# FPGA_SDRAM2.net
KiCad netlist of a schematic drawn in Altium Designer
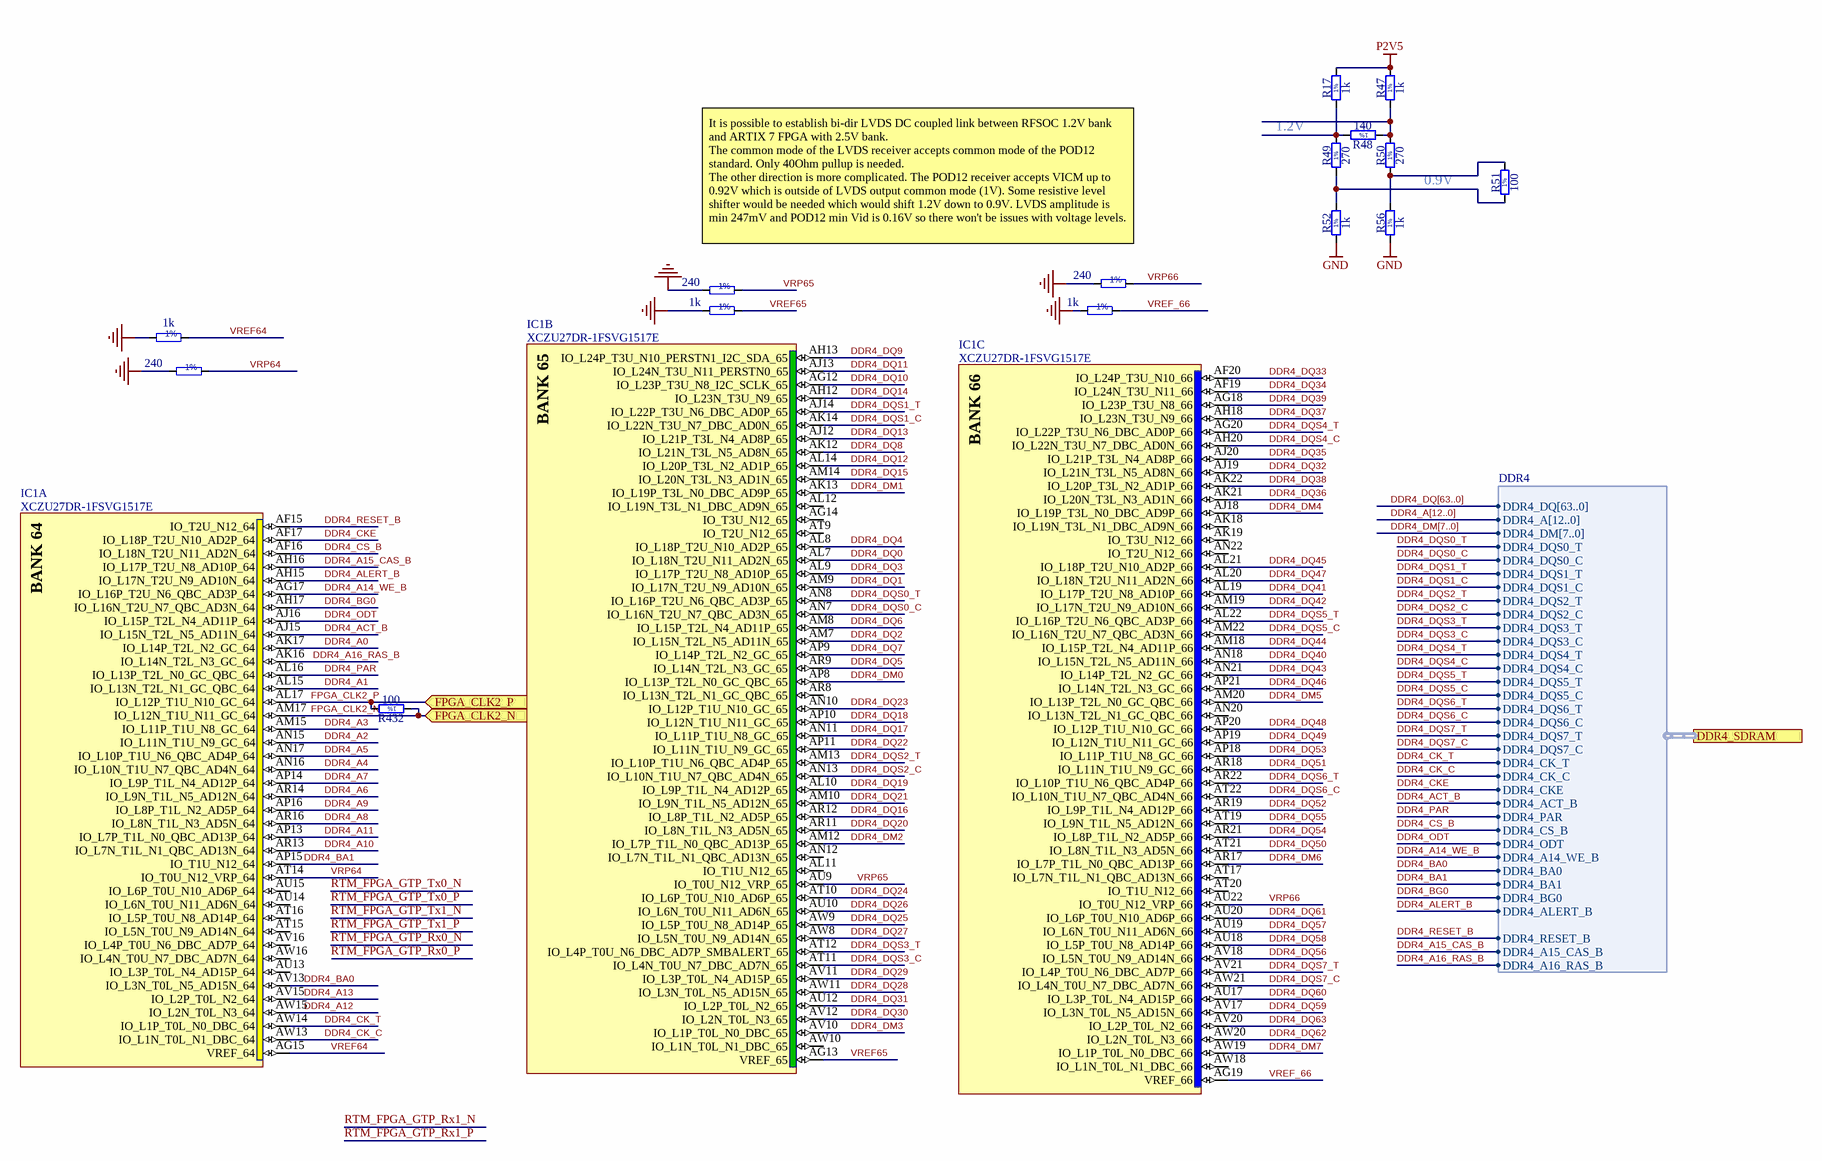
[diagram p0: FPGA_SDRAM2.SchDoc]

(export (version "E")
  (design (tool "Eeschema 10.0.6"))
  (components
    (comp (ref "IC1")
      (value "XCZU27DR-1FSVG1517E")
      (footprint "XILINX_FSVG1517 (XCZU27DR)")
      (fields (field (name "MANUFACTURER") "XILINX") (field (name "AUTHOR") "CERN DEM MR"))
      (libsource (lib "ICs And Semiconductors") (part "XCZU27DR-1FSVG1517E"))
    )
    (comp (ref "R1")
      (value "1k")
      (fields
        (field (name "$$NOTCOMMONPROPERTY_GENERAL PART NUMBER") "R0402_1K_1%_0.0625W_100PPM")
        (field (name "$$NOTCOMMONPROPERTY_MANUFACTURER1 PART NUMBER") "232270671002L")
        (field (name "MANUFACTURER") "GENERIC")
      )
      (libsource (lib "altium-import") (part "root_0__*"))
    )
    (comp (ref "R2")
      (value "240")
      (fields
        (field (name "$$NOTCOMMONPROPERTY_GENERAL PART NUMBER") "R0402_240R_1%_0.0625W_100PPM")
        (field (name "$$NOTCOMMONPROPERTY_MANUFACTURER1 PART NUMBER") "232270672401L")
        (field (name "MANUFACTURER") "GENERIC")
      )
      (libsource (lib "altium-import") (part "root_0__*"))
    )
    (comp (ref "R3")
      (value "240")
      (fields
        (field (name "$$NOTCOMMONPROPERTY_GENERAL PART NUMBER") "R0402_240R_1%_0.0625W_100PPM")
        (field (name "$$NOTCOMMONPROPERTY_MANUFACTURER1 PART NUMBER") "232270672401L")
        (field (name "MANUFACTURER") "GENERIC")
      )
      (libsource (lib "altium-import") (part "root_0__*"))
    )
    (comp (ref "R4")
      (value "240")
      (fields
        (field (name "$$NOTCOMMONPROPERTY_GENERAL PART NUMBER") "R0402_240R_1%_0.0625W_100PPM")
        (field (name "$$NOTCOMMONPROPERTY_MANUFACTURER1 PART NUMBER") "232270672401L")
        (field (name "MANUFACTURER") "GENERIC")
      )
      (libsource (lib "altium-import") (part "root_0__*"))
    )
    (comp (ref "R5")
      (value "1k")
      (fields
        (field (name "$$NOTCOMMONPROPERTY_GENERAL PART NUMBER") "R0402_1K_1%_0.0625W_100PPM")
        (field (name "$$NOTCOMMONPROPERTY_MANUFACTURER1 PART NUMBER") "232270671002L")
        (field (name "MANUFACTURER") "GENERIC")
      )
      (libsource (lib "altium-import") (part "root_0__*"))
    )
    (comp (ref "R6")
      (value "1k")
      (fields
        (field (name "$$NOTCOMMONPROPERTY_GENERAL PART NUMBER") "R0402_1K_1%_0.0625W_100PPM")
        (field (name "$$NOTCOMMONPROPERTY_MANUFACTURER1 PART NUMBER") "232270671002L")
        (field (name "MANUFACTURER") "GENERIC")
      )
      (libsource (lib "altium-import") (part "root_0__*"))
    )
    (comp (ref "R17")
      (value "1k")
      (footprint "RESC1005X40N")
      (description "Resistor - 1%")
      (fields
        (field (name "PART NUMBER") "R0402_1K_1%_0.0625W_100PPM")
        (field (name "POWER") "0.0625W")
        (field (name "AUTHOR") "CERN DEM JLC")
      )
      (libsource (lib "Resistors") (part "Resistor - 1%"))
    )
    (comp (ref "R47")
      (value "1k")
      (footprint "RESC1005X40N")
      (description "Resistor - 1%")
      (fields
        (field (name "PART NUMBER") "R0402_1K_1%_0.0625W_100PPM")
        (field (name "POWER") "0.0625W")
        (field (name "AUTHOR") "CERN DEM JLC")
      )
      (libsource (lib "Resistors") (part "Resistor - 1%"))
    )
    (comp (ref "R48")
      (value "140")
      (footprint "RESC1005X40N")
      (description "Resistor - 1%")
      (fields
        (field (name "PART NUMBER") "R0402_140R_1%_0.0625W_100PPM")
        (field (name "POWER") "0.0625W")
        (field (name "AUTHOR") "CERN DEM BC")
      )
      (libsource (lib "Resistors") (part "Resistor - 1%"))
    )
    (comp (ref "R49")
      (value "270")
      (footprint "RESC1005X40N")
      (description "Resistor - 1%")
      (fields
        (field (name "PART NUMBER") "R0402_270R_1%_0.0625W_100PPM")
        (field (name "POWER") "0.0625W")
        (field (name "AUTHOR") "CERN DEM JLC")
      )
      (libsource (lib "Resistors") (part "Resistor - 1%"))
    )
    (comp (ref "R50")
      (value "270")
      (footprint "RESC1005X40N")
      (description "Resistor - 1%")
      (fields
        (field (name "PART NUMBER") "R0402_270R_1%_0.0625W_100PPM")
        (field (name "POWER") "0.0625W")
        (field (name "AUTHOR") "CERN DEM JLC")
      )
      (libsource (lib "Resistors") (part "Resistor - 1%"))
    )
    (comp (ref "R51")
      (value "100")
      (footprint "RESC1005X40N")
      (description "Resistor - 1%")
      (fields
        (field (name "PART NUMBER") "R0402_100R_1%_0.0625W_100PPM")
        (field (name "POWER") "0.0625W")
        (field (name "AUTHOR") "CERN DEM JLC")
      )
      (libsource (lib "Resistors") (part "Resistor - 1%"))
    )
    (comp (ref "R52")
      (value "1k")
      (footprint "RESC1005X40N")
      (description "Resistor - 1%")
      (fields
        (field (name "PART NUMBER") "R0402_1K_1%_0.0625W_100PPM")
        (field (name "POWER") "0.0625W")
        (field (name "AUTHOR") "CERN DEM JLC")
      )
      (libsource (lib "Resistors") (part "Resistor - 1%"))
    )
    (comp (ref "R56")
      (value "1k")
      (footprint "RESC1005X40N")
      (description "Resistor - 1%")
      (fields
        (field (name "PART NUMBER") "R0402_1K_1%_0.0625W_100PPM")
        (field (name "POWER") "0.0625W")
        (field (name "AUTHOR") "CERN DEM JLC")
      )
      (libsource (lib "Resistors") (part "Resistor - 1%"))
    )
    (comp (ref "R432")
      (value "100")
      (footprint "RESC1005X40N")
      (description "Resistor - 1%")
      (fields
        (field (name "MANUFACTURER PART NUMBER") "R0402_100R_1%_0.0625W_100PPM")
        (field (name "MANUFACTURER") "GENERIC")
        (field (name "AUTHOR") "CERN DEM JLC")
      )
      (libsource (lib "Resistors") (part "Resistor - 1%"))
    )
  )
  (nets
    (net (code "2") (name "/DDR4_A0") (class "Default")
      (node (ref "IC1") (pin "AK17") (pinfunction "IO_L14P_T2L_N2_GC_64_AK17") (pintype "bidirectional"))
    )
    (net (code "3") (name "/DDR4_A1") (class "Default")
      (node (ref "IC1") (pin "AL15") (pinfunction "IO_L13N_T2L_N1_GC_QBC_64_AL15") (pintype "bidirectional"))
    )
    (net (code "4") (name "/DDR4_A2") (class "Default")
      (node (ref "IC1") (pin "AN15") (pinfunction "IO_L11N_T1U_N9_GC_64_AN15") (pintype "bidirectional"))
    )
    (net (code "5") (name "/DDR4_A3") (class "Default")
      (node (ref "IC1") (pin "AM15") (pinfunction "IO_L11P_T1U_N8_GC_64_AM15") (pintype "bidirectional"))
    )
    (net (code "6") (name "/DDR4_A4") (class "Default")
      (node (ref "IC1") (pin "AN16") (pinfunction "IO_L10N_T1U_N7_QBC_AD4N_64_AN16") (pintype "bidirectional"))
    )
    (net (code "7") (name "/DDR4_A5") (class "Default")
      (node (ref "IC1") (pin "AN17") (pinfunction "IO_L10P_T1U_N6_QBC_AD4P_64_AN17") (pintype "bidirectional"))
    )
    (net (code "8") (name "/DDR4_A6") (class "Default")
      (node (ref "IC1") (pin "AR14") (pinfunction "IO_L9N_T1L_N5_AD12N_64_AR14") (pintype "bidirectional"))
    )
    (net (code "9") (name "/DDR4_A7") (class "Default")
      (node (ref "IC1") (pin "AP14") (pinfunction "IO_L9P_T1L_N4_AD12P_64_AP14") (pintype "bidirectional"))
    )
    (net (code "10") (name "/DDR4_A8") (class "Default")
      (node (ref "IC1") (pin "AR16") (pinfunction "IO_L8N_T1L_N3_AD5N_64_AR16") (pintype "bidirectional"))
    )
    (net (code "11") (name "/DDR4_A9") (class "Default")
      (node (ref "IC1") (pin "AP16") (pinfunction "IO_L8P_T1L_N2_AD5P_64_AP16") (pintype "bidirectional"))
    )
    (net (code "12") (name "/DDR4_A10") (class "Default")
      (node (ref "IC1") (pin "AR13") (pinfunction "IO_L7N_T1L_N1_QBC_AD13N_64_AR13") (pintype "bidirectional"))
    )
    (net (code "13") (name "/DDR4_A11") (class "Default")
      (node (ref "IC1") (pin "AP13") (pinfunction "IO_L7P_T1L_N0_QBC_AD13P_64_AP13") (pintype "bidirectional"))
    )
    (net (code "14") (name "/DDR4_A12") (class "Default")
      (node (ref "IC1") (pin "AW15") (pinfunction "IO_L2N_T0L_N3_64_AW15") (pintype "bidirectional"))
    )
    (net (code "15") (name "/DDR4_A13") (class "Default")
      (node (ref "IC1") (pin "AV15") (pinfunction "IO_L2P_T0L_N2_64_AV15") (pintype "bidirectional"))
    )
    (net (code "16") (name "/DDR4_A14_WE_B") (class "Default")
      (node (ref "IC1") (pin "AG17") (pinfunction "IO_L16P_T2U_N6_QBC_AD3P_64_AG17") (pintype "bidirectional"))
    )
    (net (code "17") (name "/DDR4_A15_CAS_B") (class "Default")
      (node (ref "IC1") (pin "AH16") (pinfunction "IO_L17P_T2U_N8_AD10P_64_AH16") (pintype "bidirectional"))
    )
    (net (code "18") (name "/DDR4_A16_RAS_B") (class "Default")
      (node (ref "IC1") (pin "AK16") (pinfunction "IO_L14N_T2L_N3_GC_64_AK16") (pintype "bidirectional"))
    )
    (net (code "19") (name "/DDR4_ACT_B") (class "Default")
      (node (ref "IC1") (pin "AJ15") (pinfunction "IO_L15N_T2L_N5_AD11N_64_AJ15") (pintype "bidirectional"))
    )
    (net (code "20") (name "/DDR4_ALERT_B") (class "Default")
      (node (ref "IC1") (pin "AH15") (pinfunction "IO_L17N_T2U_N9_AD10N_64_AH15") (pintype "bidirectional"))
    )
    (net (code "22") (name "/DDR4_BA0") (class "Default")
      (node (ref "IC1") (pin "AV13") (pinfunction "IO_L3N_T0L_N5_AD15N_64_AV13") (pintype "bidirectional"))
    )
    (net (code "23") (name "/DDR4_BA1") (class "Default")
      (node (ref "IC1") (pin "AP15") (pinfunction "IO_T1U_N12_64_AP15") (pintype "bidirectional"))
    )
    (net (code "24") (name "/DDR4_BG0") (class "Default")
      (node (ref "IC1") (pin "AH17") (pinfunction "IO_L16N_T2U_N7_QBC_AD3N_64_AH17") (pintype "bidirectional"))
    )
    (net (code "25") (name "/DDR4_CKE") (class "Default")
      (node (ref "IC1") (pin "AF17") (pinfunction "IO_L18P_T2U_N10_AD2P_64_AF17") (pintype "bidirectional"))
    )
    (net (code "26") (name "/DDR4_CK_C") (class "Default")
      (node (ref "IC1") (pin "AW13") (pinfunction "IO_L1N_T0L_N1_DBC_64_AW13") (pintype "bidirectional"))
    )
    (net (code "27") (name "/DDR4_CK_T") (class "Default")
      (node (ref "IC1") (pin "AW14") (pinfunction "IO_L1P_T0L_N0_DBC_64_AW14") (pintype "bidirectional"))
    )
    (net (code "28") (name "/DDR4_CS_B") (class "Default")
      (node (ref "IC1") (pin "AF16") (pinfunction "IO_L18N_T2U_N11_AD2N_64_AF16") (pintype "bidirectional"))
    )
    (net (code "29") (name "/DDR4_DM0") (class "Default")
      (node (ref "IC1") (pin "AP8") (pinfunction "IO_L13P_T2L_N0_GC_QBC_65_AP8") (pintype "bidirectional"))
    )
    (net (code "30") (name "/DDR4_DM1") (class "Default")
      (node (ref "IC1") (pin "AK13") (pinfunction "IO_L19P_T3L_N0_DBC_AD9P_65_AK13") (pintype "bidirectional"))
    )
    (net (code "31") (name "/DDR4_DM2") (class "Default")
      (node (ref "IC1") (pin "AM12") (pinfunction "IO_L7P_T1L_N0_QBC_AD13P_65_AM12") (pintype "bidirectional"))
    )
    (net (code "32") (name "/DDR4_DM3") (class "Default")
      (node (ref "IC1") (pin "AV10") (pinfunction "IO_L1P_T0L_N0_DBC_65_AV10") (pintype "bidirectional"))
    )
    (net (code "33") (name "/DDR4_DM4") (class "Default")
      (node (ref "IC1") (pin "AJ18") (pinfunction "IO_L19P_T3L_N0_DBC_AD9P_66_AJ18") (pintype "bidirectional"))
    )
    (net (code "34") (name "/DDR4_DM5") (class "Default")
      (node (ref "IC1") (pin "AM20") (pinfunction "IO_L13P_T2L_N0_GC_QBC_66_AM20") (pintype "bidirectional"))
    )
    (net (code "35") (name "/DDR4_DM6") (class "Default")
      (node (ref "IC1") (pin "AR17") (pinfunction "IO_L7P_T1L_N0_QBC_AD13P_66_AR17") (pintype "bidirectional"))
    )
    (net (code "36") (name "/DDR4_DM7") (class "Default")
      (node (ref "IC1") (pin "AW19") (pinfunction "IO_L1P_T0L_N0_DBC_66_AW19") (pintype "bidirectional"))
    )
    (net (code "37") (name "/DDR4_DQ0") (class "Default")
      (node (ref "IC1") (pin "AL7") (pinfunction "IO_L18N_T2U_N11_AD2N_65_AL7") (pintype "bidirectional"))
    )
    (net (code "38") (name "/DDR4_DQ1") (class "Default")
      (node (ref "IC1") (pin "AM9") (pinfunction "IO_L17N_T2U_N9_AD10N_65_AM9") (pintype "bidirectional"))
    )
    (net (code "39") (name "/DDR4_DQ2") (class "Default")
      (node (ref "IC1") (pin "AM7") (pinfunction "IO_L15N_T2L_N5_AD11N_65_AM7") (pintype "bidirectional"))
    )
    (net (code "40") (name "/DDR4_DQ3") (class "Default")
      (node (ref "IC1") (pin "AL9") (pinfunction "IO_L17P_T2U_N8_AD10P_65_AL9") (pintype "bidirectional"))
    )
    (net (code "41") (name "/DDR4_DQ4") (class "Default")
      (node (ref "IC1") (pin "AL8") (pinfunction "IO_L18P_T2U_N10_AD2P_65_AL8") (pintype "bidirectional"))
    )
    (net (code "42") (name "/DDR4_DQ5") (class "Default")
      (node (ref "IC1") (pin "AR9") (pinfunction "IO_L14N_T2L_N3_GC_65_AR9") (pintype "bidirectional"))
    )
    (net (code "43") (name "/DDR4_DQ6") (class "Default")
      (node (ref "IC1") (pin "AM8") (pinfunction "IO_L15P_T2L_N4_AD11P_65_AM8") (pintype "bidirectional"))
    )
    (net (code "44") (name "/DDR4_DQ7") (class "Default")
      (node (ref "IC1") (pin "AP9") (pinfunction "IO_L14P_T2L_N2_GC_65_AP9") (pintype "bidirectional"))
    )
    (net (code "45") (name "/DDR4_DQ8") (class "Default")
      (node (ref "IC1") (pin "AK12") (pinfunction "IO_L21N_T3L_N5_AD8N_65_AK12") (pintype "bidirectional"))
    )
    (net (code "46") (name "/DDR4_DQ9") (class "Default")
      (node (ref "IC1") (pin "AH13") (pinfunction "IO_L24P_T3U_N10_PERSTN1_I2C_SDA_65_AH13") (pintype "bidirectional"))
    )
    (net (code "47") (name "/DDR4_DQ10") (class "Default")
      (node (ref "IC1") (pin "AG12") (pinfunction "IO_L23P_T3U_N8_I2C_SCLK_65_AG12") (pintype "bidirectional"))
    )
    (net (code "48") (name "/DDR4_DQ11") (class "Default")
      (node (ref "IC1") (pin "AJ13") (pinfunction "IO_L24N_T3U_N11_PERSTN0_65_AJ13") (pintype "bidirectional"))
    )
    (net (code "49") (name "/DDR4_DQ12") (class "Default")
      (node (ref "IC1") (pin "AL14") (pinfunction "IO_L20P_T3L_N2_AD1P_65_AL14") (pintype "bidirectional"))
    )
    (net (code "50") (name "/DDR4_DQ13") (class "Default")
      (node (ref "IC1") (pin "AJ12") (pinfunction "IO_L21P_T3L_N4_AD8P_65_AJ12") (pintype "bidirectional"))
    )
    (net (code "51") (name "/DDR4_DQ14") (class "Default")
      (node (ref "IC1") (pin "AH12") (pinfunction "IO_L23N_T3U_N9_65_AH12") (pintype "bidirectional"))
    )
    (net (code "52") (name "/DDR4_DQ15") (class "Default")
      (node (ref "IC1") (pin "AM14") (pinfunction "IO_L20N_T3L_N3_AD1N_65_AM14") (pintype "bidirectional"))
    )
    (net (code "53") (name "/DDR4_DQ16") (class "Default")
      (node (ref "IC1") (pin "AR12") (pinfunction "IO_L8P_T1L_N2_AD5P_65_AR12") (pintype "bidirectional"))
    )
    (net (code "54") (name "/DDR4_DQ17") (class "Default")
      (node (ref "IC1") (pin "AN11") (pinfunction "IO_L11P_T1U_N8_GC_65_AN11") (pintype "bidirectional"))
    )
    (net (code "55") (name "/DDR4_DQ18") (class "Default")
      (node (ref "IC1") (pin "AP10") (pinfunction "IO_L12N_T1U_N11_GC_65_AP10") (pintype "bidirectional"))
    )
    (net (code "56") (name "/DDR4_DQ19") (class "Default")
      (node (ref "IC1") (pin "AL10") (pinfunction "IO_L9P_T1L_N4_AD12P_65_AL10") (pintype "bidirectional"))
    )
    (net (code "57") (name "/DDR4_DQ20") (class "Default")
      (node (ref "IC1") (pin "AR11") (pinfunction "IO_L8N_T1L_N3_AD5N_65_AR11") (pintype "bidirectional"))
    )
    (net (code "58") (name "/DDR4_DQ21") (class "Default")
      (node (ref "IC1") (pin "AM10") (pinfunction "IO_L9N_T1L_N5_AD12N_65_AM10") (pintype "bidirectional"))
    )
    (net (code "59") (name "/DDR4_DQ22") (class "Default")
      (node (ref "IC1") (pin "AP11") (pinfunction "IO_L11N_T1U_N9_GC_65_AP11") (pintype "bidirectional"))
    )
    (net (code "60") (name "/DDR4_DQ23") (class "Default")
      (node (ref "IC1") (pin "AN10") (pinfunction "IO_L12P_T1U_N10_GC_65_AN10") (pintype "bidirectional"))
    )
    (net (code "61") (name "/DDR4_DQ24") (class "Default")
      (node (ref "IC1") (pin "AT10") (pinfunction "IO_L6P_T0U_N10_AD6P_65_AT10") (pintype "bidirectional"))
    )
    (net (code "62") (name "/DDR4_DQ25") (class "Default")
      (node (ref "IC1") (pin "AW9") (pinfunction "IO_L5P_T0U_N8_AD14P_65_AW9") (pintype "bidirectional"))
    )
    (net (code "63") (name "/DDR4_DQ26") (class "Default")
      (node (ref "IC1") (pin "AU10") (pinfunction "IO_L6N_T0U_N11_AD6N_65_AU10") (pintype "bidirectional"))
    )
    (net (code "64") (name "/DDR4_DQ27") (class "Default")
      (node (ref "IC1") (pin "AW8") (pinfunction "IO_L5N_T0U_N9_AD14N_65_AW8") (pintype "bidirectional"))
    )
    (net (code "65") (name "/DDR4_DQ28") (class "Default")
      (node (ref "IC1") (pin "AW11") (pinfunction "IO_L3N_T0L_N5_AD15N_65_AW11") (pintype "bidirectional"))
    )
    (net (code "66") (name "/DDR4_DQ29") (class "Default")
      (node (ref "IC1") (pin "AV11") (pinfunction "IO_L3P_T0L_N4_AD15P_65_AV11") (pintype "bidirectional"))
    )
    (net (code "67") (name "/DDR4_DQ30") (class "Default")
      (node (ref "IC1") (pin "AV12") (pinfunction "IO_L2N_T0L_N3_65_AV12") (pintype "bidirectional"))
    )
    (net (code "68") (name "/DDR4_DQ31") (class "Default")
      (node (ref "IC1") (pin "AU12") (pinfunction "IO_L2P_T0L_N2_65_AU12") (pintype "bidirectional"))
    )
    (net (code "69") (name "/DDR4_DQ32") (class "Default")
      (node (ref "IC1") (pin "AJ19") (pinfunction "IO_L21N_T3L_N5_AD8N_66_AJ19") (pintype "bidirectional"))
    )
    (net (code "70") (name "/DDR4_DQ33") (class "Default")
      (node (ref "IC1") (pin "AF20") (pinfunction "IO_L24P_T3U_N10_66_AF20") (pintype "bidirectional"))
    )
    (net (code "71") (name "/DDR4_DQ34") (class "Default")
      (node (ref "IC1") (pin "AF19") (pinfunction "IO_L24N_T3U_N11_66_AF19") (pintype "bidirectional"))
    )
    (net (code "72") (name "/DDR4_DQ35") (class "Default")
      (node (ref "IC1") (pin "AJ20") (pinfunction "IO_L21P_T3L_N4_AD8P_66_AJ20") (pintype "bidirectional"))
    )
    (net (code "73") (name "/DDR4_DQ36") (class "Default")
      (node (ref "IC1") (pin "AK21") (pinfunction "IO_L20N_T3L_N3_AD1N_66_AK21") (pintype "bidirectional"))
    )
    (net (code "74") (name "/DDR4_DQ37") (class "Default")
      (node (ref "IC1") (pin "AH18") (pinfunction "IO_L23N_T3U_N9_66_AH18") (pintype "bidirectional"))
    )
    (net (code "75") (name "/DDR4_DQ38") (class "Default")
      (node (ref "IC1") (pin "AK22") (pinfunction "IO_L20P_T3L_N2_AD1P_66_AK22") (pintype "bidirectional"))
    )
    (net (code "76") (name "/DDR4_DQ39") (class "Default")
      (node (ref "IC1") (pin "AG18") (pinfunction "IO_L23P_T3U_N8_66_AG18") (pintype "bidirectional"))
    )
    (net (code "77") (name "/DDR4_DQ40") (class "Default")
      (node (ref "IC1") (pin "AN18") (pinfunction "IO_L15N_T2L_N5_AD11N_66_AN18") (pintype "bidirectional"))
    )
    (net (code "78") (name "/DDR4_DQ41") (class "Default")
      (node (ref "IC1") (pin "AL19") (pinfunction "IO_L17P_T2U_N8_AD10P_66_AL19") (pintype "bidirectional"))
    )
    (net (code "79") (name "/DDR4_DQ42") (class "Default")
      (node (ref "IC1") (pin "AM19") (pinfunction "IO_L17N_T2U_N9_AD10N_66_AM19") (pintype "bidirectional"))
    )
    (net (code "80") (name "/DDR4_DQ43") (class "Default")
      (node (ref "IC1") (pin "AN21") (pinfunction "IO_L14P_T2L_N2_GC_66_AN21") (pintype "bidirectional"))
    )
    (net (code "81") (name "/DDR4_DQ44") (class "Default")
      (node (ref "IC1") (pin "AM18") (pinfunction "IO_L15P_T2L_N4_AD11P_66_AM18") (pintype "bidirectional"))
    )
    (net (code "82") (name "/DDR4_DQ45") (class "Default")
      (node (ref "IC1") (pin "AL21") (pinfunction "IO_L18P_T2U_N10_AD2P_66_AL21") (pintype "bidirectional"))
    )
    (net (code "83") (name "/DDR4_DQ46") (class "Default")
      (node (ref "IC1") (pin "AP21") (pinfunction "IO_L14N_T2L_N3_GC_66_AP21") (pintype "bidirectional"))
    )
    (net (code "84") (name "/DDR4_DQ47") (class "Default")
      (node (ref "IC1") (pin "AL20") (pinfunction "IO_L18N_T2U_N11_AD2N_66_AL20") (pintype "bidirectional"))
    )
    (net (code "85") (name "/DDR4_DQ48") (class "Default")
      (node (ref "IC1") (pin "AP20") (pinfunction "IO_L12P_T1U_N10_GC_66_AP20") (pintype "bidirectional"))
    )
    (net (code "86") (name "/DDR4_DQ49") (class "Default")
      (node (ref "IC1") (pin "AP19") (pinfunction "IO_L12N_T1U_N11_GC_66_AP19") (pintype "bidirectional"))
    )
    (net (code "87") (name "/DDR4_DQ50") (class "Default")
      (node (ref "IC1") (pin "AT21") (pinfunction "IO_L8N_T1L_N3_AD5N_66_AT21") (pintype "bidirectional"))
    )
    (net (code "88") (name "/DDR4_DQ51") (class "Default")
      (node (ref "IC1") (pin "AR18") (pinfunction "IO_L11N_T1U_N9_GC_66_AR18") (pintype "bidirectional"))
    )
    (net (code "89") (name "/DDR4_DQ52") (class "Default")
      (node (ref "IC1") (pin "AR19") (pinfunction "IO_L9P_T1L_N4_AD12P_66_AR19") (pintype "bidirectional"))
    )
    (net (code "90") (name "/DDR4_DQ53") (class "Default")
      (node (ref "IC1") (pin "AP18") (pinfunction "IO_L11P_T1U_N8_GC_66_AP18") (pintype "bidirectional"))
    )
    (net (code "91") (name "/DDR4_DQ54") (class "Default")
      (node (ref "IC1") (pin "AR21") (pinfunction "IO_L8P_T1L_N2_AD5P_66_AR21") (pintype "bidirectional"))
    )
    (net (code "92") (name "/DDR4_DQ55") (class "Default")
      (node (ref "IC1") (pin "AT19") (pinfunction "IO_L9N_T1L_N5_AD12N_66_AT19") (pintype "bidirectional"))
    )
    (net (code "93") (name "/DDR4_DQ56") (class "Default")
      (node (ref "IC1") (pin "AV18") (pinfunction "IO_L5N_T0U_N9_AD14N_66_AV18") (pintype "bidirectional"))
    )
    (net (code "94") (name "/DDR4_DQ57") (class "Default")
      (node (ref "IC1") (pin "AU19") (pinfunction "IO_L6N_T0U_N11_AD6N_66_AU19") (pintype "bidirectional"))
    )
    (net (code "95") (name "/DDR4_DQ58") (class "Default")
      (node (ref "IC1") (pin "AU18") (pinfunction "IO_L5P_T0U_N8_AD14P_66_AU18") (pintype "bidirectional"))
    )
    (net (code "96") (name "/DDR4_DQ59") (class "Default")
      (node (ref "IC1") (pin "AV17") (pinfunction "IO_L3N_T0L_N5_AD15N_66_AV17") (pintype "bidirectional"))
    )
    (net (code "97") (name "/DDR4_DQ60") (class "Default")
      (node (ref "IC1") (pin "AU17") (pinfunction "IO_L3P_T0L_N4_AD15P_66_AU17") (pintype "bidirectional"))
    )
    (net (code "98") (name "/DDR4_DQ61") (class "Default")
      (node (ref "IC1") (pin "AU20") (pinfunction "IO_L6P_T0U_N10_AD6P_66_AU20") (pintype "bidirectional"))
    )
    (net (code "99") (name "/DDR4_DQ62") (class "Default")
      (node (ref "IC1") (pin "AW20") (pinfunction "IO_L2N_T0L_N3_66_AW20") (pintype "bidirectional"))
    )
    (net (code "100") (name "/DDR4_DQ63") (class "Default")
      (node (ref "IC1") (pin "AV20") (pinfunction "IO_L2P_T0L_N2_66_AV20") (pintype "bidirectional"))
    )
    (net (code "101") (name "/DDR4_DQS0_C") (class "Default")
      (node (ref "IC1") (pin "AN7") (pinfunction "IO_L16N_T2U_N7_QBC_AD3N_65_AN7") (pintype "bidirectional"))
    )
    (net (code "102") (name "/DDR4_DQS0_T") (class "Default")
      (node (ref "IC1") (pin "AN8") (pinfunction "IO_L16P_T2U_N6_QBC_AD3P_65_AN8") (pintype "bidirectional"))
    )
    (net (code "103") (name "/DDR4_DQS1_C") (class "Default")
      (node (ref "IC1") (pin "AK14") (pinfunction "IO_L22N_T3U_N7_DBC_AD0N_65_AK14") (pintype "bidirectional"))
    )
    (net (code "104") (name "/DDR4_DQS1_T") (class "Default")
      (node (ref "IC1") (pin "AJ14") (pinfunction "IO_L22P_T3U_N6_DBC_AD0P_65_AJ14") (pintype "bidirectional"))
    )
    (net (code "105") (name "/DDR4_DQS2_C") (class "Default")
      (node (ref "IC1") (pin "AN13") (pinfunction "IO_L10N_T1U_N7_QBC_AD4N_65_AN13") (pintype "bidirectional"))
    )
    (net (code "106") (name "/DDR4_DQS2_T") (class "Default")
      (node (ref "IC1") (pin "AM13") (pinfunction "IO_L10P_T1U_N6_QBC_AD4P_65_AM13") (pintype "bidirectional"))
    )
    (net (code "107") (name "/DDR4_DQS3_C") (class "Default")
      (node (ref "IC1") (pin "AT11") (pinfunction "IO_L4N_T0U_N7_DBC_AD7N_65_AT11") (pintype "bidirectional"))
    )
    (net (code "108") (name "/DDR4_DQS3_T") (class "Default")
      (node (ref "IC1") (pin "AT12") (pinfunction "IO_L4P_T0U_N6_DBC_AD7P_SMBALERT_65_AT12") (pintype "bidirectional"))
    )
    (net (code "109") (name "/DDR4_DQS4_C") (class "Default")
      (node (ref "IC1") (pin "AH20") (pinfunction "IO_L22N_T3U_N7_DBC_AD0N_66_AH20") (pintype "bidirectional"))
    )
    (net (code "110") (name "/DDR4_DQS4_T") (class "Default")
      (node (ref "IC1") (pin "AG20") (pinfunction "IO_L22P_T3U_N6_DBC_AD0P_66_AG20") (pintype "bidirectional"))
    )
    (net (code "111") (name "/DDR4_DQS5_C") (class "Default")
      (node (ref "IC1") (pin "AM22") (pinfunction "IO_L16N_T2U_N7_QBC_AD3N_66_AM22") (pintype "bidirectional"))
    )
    (net (code "112") (name "/DDR4_DQS5_T") (class "Default")
      (node (ref "IC1") (pin "AL22") (pinfunction "IO_L16P_T2U_N6_QBC_AD3P_66_AL22") (pintype "bidirectional"))
    )
    (net (code "113") (name "/DDR4_DQS6_C") (class "Default")
      (node (ref "IC1") (pin "AT22") (pinfunction "IO_L10N_T1U_N7_QBC_AD4N_66_AT22") (pintype "bidirectional"))
    )
    (net (code "114") (name "/DDR4_DQS6_T") (class "Default")
      (node (ref "IC1") (pin "AR22") (pinfunction "IO_L10P_T1U_N6_QBC_AD4P_66_AR22") (pintype "bidirectional"))
    )
    (net (code "115") (name "/DDR4_DQS7_C") (class "Default")
      (node (ref "IC1") (pin "AW21") (pinfunction "IO_L4N_T0U_N7_DBC_AD7N_66_AW21") (pintype "bidirectional"))
    )
    (net (code "116") (name "/DDR4_DQS7_T") (class "Default")
      (node (ref "IC1") (pin "AV21") (pinfunction "IO_L4P_T0U_N6_DBC_AD7P_66_AV21") (pintype "bidirectional"))
    )
    (net (code "118") (name "/DDR4_ODT") (class "Default")
      (node (ref "IC1") (pin "AJ16") (pinfunction "IO_L15P_T2L_N4_AD11P_64_AJ16") (pintype "bidirectional"))
    )
    (net (code "119") (name "/DDR4_PAR") (class "Default")
      (node (ref "IC1") (pin "AL16") (pinfunction "IO_L13P_T2L_N0_GC_QBC_64_AL16") (pintype "bidirectional"))
    )
    (net (code "120") (name "/DDR4_RESET_B") (class "Default")
      (node (ref "IC1") (pin "AF15") (pinfunction "IO_T2U_N12_64_AF15") (pintype "bidirectional"))
    )
    (net (code "122") (name "/FPGA_CLK2_N") (class "Default")
      (node (ref "IC1") (pin "AM17") (pinfunction "IO_L12N_T1U_N11_GC_64_AM17") (pintype "bidirectional"))
      (node (ref "R432") (pin "2") (pinfunction "2_2") (pintype "passive"))
    )
    (net (code "123") (name "/FPGA_CLK2_P") (class "Default")
      (node (ref "IC1") (pin "AL17") (pinfunction "IO_L12P_T1U_N10_GC_64_AL17") (pintype "bidirectional"))
      (node (ref "R432") (pin "1") (pinfunction "1_1") (pintype "passive"))
    )
    (net (code "132") (name "/VREF64") (class "Default")
      (node (ref "IC1") (pin "AG15") (pinfunction "VREF_64_AG15") (pintype "bidirectional"))
      (node (ref "R1") (pin "2") (pinfunction "2_2") (pintype "passive"))
    )
    (net (code "133") (name "/VREF65") (class "Default")
      (node (ref "IC1") (pin "AG13") (pinfunction "VREF_65_AG13") (pintype "bidirectional"))
      (node (ref "R5") (pin "2") (pinfunction "2_2") (pintype "passive"))
    )
    (net (code "134") (name "/VREF_66") (class "Default")
      (node (ref "IC1") (pin "AG19") (pinfunction "VREF_66_AG19") (pintype "bidirectional"))
      (node (ref "R6") (pin "2") (pinfunction "2_2") (pintype "passive"))
    )
    (net (code "135") (name "/VRP64") (class "Default")
      (node (ref "IC1") (pin "AT14") (pinfunction "IO_T0U_N12_VRP_64_AT14") (pintype "bidirectional"))
      (node (ref "R4") (pin "2") (pinfunction "2_2") (pintype "passive"))
    )
    (net (code "136") (name "/VRP65") (class "Default")
      (node (ref "IC1") (pin "AU9") (pinfunction "IO_T0U_N12_VRP_65_AU9") (pintype "bidirectional"))
      (node (ref "R3") (pin "2") (pinfunction "2_2") (pintype "passive"))
    )
    (net (code "137") (name "/VRP66") (class "Default")
      (node (ref "IC1") (pin "AU22") (pinfunction "IO_T0U_N12_VRP_66_AU22") (pintype "bidirectional"))
      (node (ref "R2") (pin "2") (pinfunction "2_2") (pintype "passive"))
    )
    (net (code "139") (name "GND") (class "Default")
      (node (ref "R1") (pin "1") (pinfunction "1_1") (pintype "passive"))
      (node (ref "R2") (pin "1") (pinfunction "1_1") (pintype "passive"))
      (node (ref "R3") (pin "1") (pinfunction "1_1") (pintype "passive"))
      (node (ref "R4") (pin "1") (pinfunction "1_1") (pintype "passive"))
      (node (ref "R5") (pin "1") (pinfunction "1_1") (pintype "passive"))
      (node (ref "R52") (pin "1") (pinfunction "1_1") (pintype "passive"))
      (node (ref "R56") (pin "1") (pinfunction "1_1") (pintype "passive"))
      (node (ref "R6") (pin "1") (pinfunction "1_1") (pintype "passive"))
    )
    (net (code "140") (name "Net-(R17-Pad1)") (class "Default")
      (node (ref "R17") (pin "1") (pinfunction "1_1") (pintype "passive"))
      (node (ref "R48") (pin "2") (pinfunction "2_2") (pintype "passive"))
      (node (ref "R49") (pin "2") (pinfunction "2_2") (pintype "passive"))
    )
    (net (code "141") (name "Net-(R47-Pad1)") (class "Default")
      (node (ref "R47") (pin "1") (pinfunction "1_1") (pintype "passive"))
      (node (ref "R48") (pin "1") (pinfunction "1_1") (pintype "passive"))
      (node (ref "R50") (pin "2") (pinfunction "2_2") (pintype "passive"))
    )
    (net (code "142") (name "Net-(R49-Pad1)") (class "Default")
      (node (ref "R49") (pin "1") (pinfunction "1_1") (pintype "passive"))
      (node (ref "R51") (pin "1") (pinfunction "1_1") (pintype "passive"))
      (node (ref "R52") (pin "2") (pinfunction "2_2") (pintype "passive"))
    )
    (net (code "143") (name "Net-(R50-Pad1)") (class "Default")
      (node (ref "R50") (pin "1") (pinfunction "1_1") (pintype "passive"))
      (node (ref "R51") (pin "2") (pinfunction "2_2") (pintype "passive"))
      (node (ref "R56") (pin "2") (pinfunction "2_2") (pintype "passive"))
    )
    (net (code "144") (name "P2V5") (class "Default")
      (node (ref "R17") (pin "2") (pinfunction "2_2") (pintype "passive"))
      (node (ref "R47") (pin "2") (pinfunction "2_2") (pintype "passive"))
    )
    (net (code "145") (name "unconnected-(IC1A-IO_L3P_T0L_N4_AD15P_64-PadAU13)") (class "Default")
      (node (ref "IC1") (pin "AU13") (pinfunction "IO_L3P_T0L_N4_AD15P_64_AU13") (pintype "bidirectional"))
    )
    (net (code "146") (name "unconnected-(IC1A-IO_L4N_T0U_N7_DBC_AD7N_64-PadAW16)") (class "Default")
      (node (ref "IC1") (pin "AW16") (pinfunction "IO_L4N_T0U_N7_DBC_AD7N_64_AW16") (pintype "bidirectional"))
    )
    (net (code "147") (name "unconnected-(IC1A-IO_L4P_T0U_N6_DBC_AD7P_64-PadAV16)") (class "Default")
      (node (ref "IC1") (pin "AV16") (pinfunction "IO_L4P_T0U_N6_DBC_AD7P_64_AV16") (pintype "bidirectional"))
    )
    (net (code "148") (name "unconnected-(IC1A-IO_L5N_T0U_N9_AD14N_64-PadAT15)") (class "Default")
      (node (ref "IC1") (pin "AT15") (pinfunction "IO_L5N_T0U_N9_AD14N_64_AT15") (pintype "bidirectional"))
    )
    (net (code "149") (name "unconnected-(IC1A-IO_L5P_T0U_N8_AD14P_64-PadAT16)") (class "Default")
      (node (ref "IC1") (pin "AT16") (pinfunction "IO_L5P_T0U_N8_AD14P_64_AT16") (pintype "bidirectional"))
    )
    (net (code "150") (name "unconnected-(IC1A-IO_L6N_T0U_N11_AD6N_64-PadAU14)") (class "Default")
      (node (ref "IC1") (pin "AU14") (pinfunction "IO_L6N_T0U_N11_AD6N_64_AU14") (pintype "bidirectional"))
    )
    (net (code "151") (name "unconnected-(IC1A-IO_L6P_T0U_N10_AD6P_64-PadAU15)") (class "Default")
      (node (ref "IC1") (pin "AU15") (pinfunction "IO_L6P_T0U_N10_AD6P_64_AU15") (pintype "bidirectional"))
    )
    (net (code "152") (name "unconnected-(IC1B-IO_L1N_T0L_N1_DBC_65-PadAW10)") (class "Default")
      (node (ref "IC1") (pin "AW10") (pinfunction "IO_L1N_T0L_N1_DBC_65_AW10") (pintype "bidirectional"))
    )
    (net (code "153") (name "unconnected-(IC1B-IO_L7N_T1L_N1_QBC_AD13N_65-PadAN12)") (class "Default")
      (node (ref "IC1") (pin "AN12") (pinfunction "IO_L7N_T1L_N1_QBC_AD13N_65_AN12") (pintype "bidirectional"))
    )
    (net (code "154") (name "unconnected-(IC1B-IO_L13N_T2L_N1_GC_QBC_65-PadAR8)") (class "Default")
      (node (ref "IC1") (pin "AR8") (pinfunction "IO_L13N_T2L_N1_GC_QBC_65_AR8") (pintype "bidirectional"))
    )
    (net (code "155") (name "unconnected-(IC1B-IO_L19N_T3L_N1_DBC_AD9N_65-PadAL12)") (class "Default")
      (node (ref "IC1") (pin "AL12") (pinfunction "IO_L19N_T3L_N1_DBC_AD9N_65_AL12") (pintype "bidirectional"))
    )
    (net (code "156") (name "unconnected-(IC1B-IO_T1U_N12_65-PadAL11)") (class "Default")
      (node (ref "IC1") (pin "AL11") (pinfunction "IO_T1U_N12_65_AL11") (pintype "bidirectional"))
    )
    (net (code "157") (name "unconnected-(IC1B-IO_T2U_N12_65-PadAT9)") (class "Default")
      (node (ref "IC1") (pin "AT9") (pinfunction "IO_T2U_N12_65_AT9") (pintype "bidirectional"))
    )
    (net (code "158") (name "unconnected-(IC1B-IO_T3U_N12_65-PadAG14)") (class "Default")
      (node (ref "IC1") (pin "AG14") (pinfunction "IO_T3U_N12_65_AG14") (pintype "bidirectional"))
    )
    (net (code "159") (name "unconnected-(IC1C-IO_L1N_T0L_N1_DBC_66-PadAW18)") (class "Default")
      (node (ref "IC1") (pin "AW18") (pinfunction "IO_L1N_T0L_N1_DBC_66_AW18") (pintype "bidirectional"))
    )
    (net (code "160") (name "unconnected-(IC1C-IO_L7N_T1L_N1_QBC_AD13N_66-PadAT17)") (class "Default")
      (node (ref "IC1") (pin "AT17") (pinfunction "IO_L7N_T1L_N1_QBC_AD13N_66_AT17") (pintype "bidirectional"))
    )
    (net (code "161") (name "unconnected-(IC1C-IO_L13N_T2L_N1_GC_QBC_66-PadAN20)") (class "Default")
      (node (ref "IC1") (pin "AN20") (pinfunction "IO_L13N_T2L_N1_GC_QBC_66_AN20") (pintype "bidirectional"))
    )
    (net (code "162") (name "unconnected-(IC1C-IO_L19N_T3L_N1_DBC_AD9N_66-PadAK18)") (class "Default")
      (node (ref "IC1") (pin "AK18") (pinfunction "IO_L19N_T3L_N1_DBC_AD9N_66_AK18") (pintype "bidirectional"))
    )
    (net (code "163") (name "unconnected-(IC1C-IO_T1U_N12_66-PadAT20)") (class "Default")
      (node (ref "IC1") (pin "AT20") (pinfunction "IO_T1U_N12_66_AT20") (pintype "bidirectional"))
    )
    (net (code "164") (name "unconnected-(IC1C-IO_T2U_N12_66-PadAN22)") (class "Default")
      (node (ref "IC1") (pin "AN22") (pinfunction "IO_T2U_N12_66_AN22") (pintype "bidirectional"))
    )
    (net (code "165") (name "unconnected-(IC1C-IO_T3U_N12_66-PadAK19)") (class "Default")
      (node (ref "IC1") (pin "AK19") (pinfunction "IO_T3U_N12_66_AK19") (pintype "bidirectional"))
    )
  )
)
